# sigtest.net
KiCad netlist of a schematic drawn in EAGLE
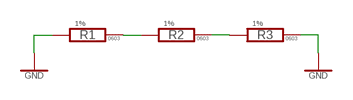
[diagram p0: schematic, sheet 1]

(export (version "E")
  (design (tool "Eeschema 10.0.6"))
  (components
    (comp (ref "R1")
      (value "R-1%-0603")
      (footprint "eagle-import:R0603")
      (fields (field (name "PACKAGE") "0603") (field (name "TOLERANCE") "1%"))
      (libsource (lib "eagle-import") (part "R-0603-1%"))
    )
    (comp (ref "R2")
      (value "R-1%-0603")
      (footprint "eagle-import:R0603")
      (fields (field (name "PACKAGE") "0603") (field (name "TOLERANCE") "1%"))
      (libsource (lib "eagle-import") (part "R-0603-1%"))
    )
    (comp (ref "R3")
      (value "R-1%-0603")
      (footprint "eagle-import:R0603")
      (fields (field (name "PACKAGE") "0603") (field (name "TOLERANCE") "1%"))
      (libsource (lib "eagle-import") (part "R-0603-1%"))
    )
  )
  (nets
    (net (code "1") (name "GND") (class "Default")
      (node (ref "R1") (pin "2") (pinfunction "2_2") (pintype "passive"))
      (node (ref "R3") (pin "1") (pinfunction "1_1") (pintype "passive"))
    )
    (net (code "2") (name "Net-(R1-Pad1)") (class "Default")
      (node (ref "R1") (pin "1") (pinfunction "1_1") (pintype "passive"))
      (node (ref "R2") (pin "2") (pinfunction "2_2") (pintype "passive"))
    )
    (net (code "3") (name "Net-(R2-Pad1)") (class "Default")
      (node (ref "R2") (pin "1") (pinfunction "1_1") (pintype "passive"))
      (node (ref "R3") (pin "2") (pinfunction "2_2") (pintype "passive"))
    )
  )
)
